# Input.net
KiCad netlist of a schematic drawn in Altium Designer
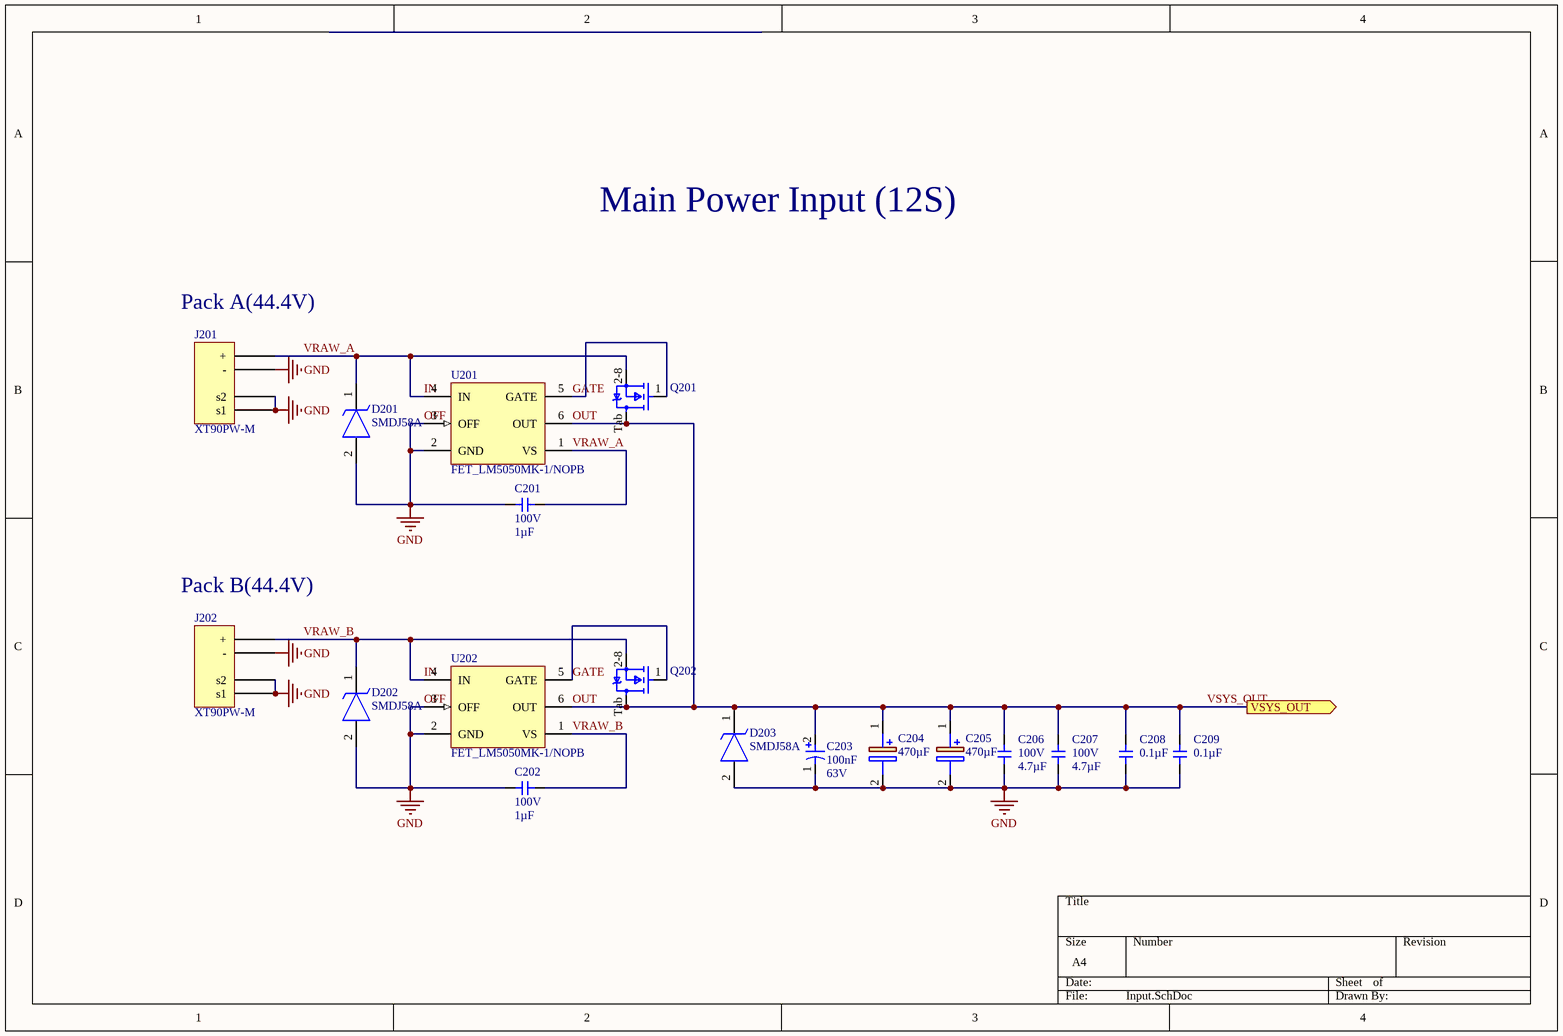
[diagram p0: Input.SchDoc]

(export (version "E")
  (design (tool "Eeschema 10.0.6"))
  (components
    (comp (ref "C201")
      (value "non-polar_Capacitor")
      (footprint "1206")
      (description "SMD type ceramic capacitor")
      (fields
        (field (name "VOLTAGE") "100V")
        (field (name "CAPACITANCE") "1µF")
        (field (name "SOURCE") "robit_passive.SchLib")
      )
      (libsource (lib "robit circuit") (part "Capacitor"))
    )
    (comp (ref "C202")
      (value "non-polar_Capacitor")
      (footprint "1206")
      (description "SMD type ceramic capacitor")
      (fields
        (field (name "VOLTAGE") "100V")
        (field (name "CAPACITANCE") "1µF")
        (field (name "SOURCE") "robit_passive.SchLib")
      )
      (libsource (lib "robit circuit") (part "Capacitor"))
    )
    (comp (ref "C203")
      (value "Capacitor_tantal")
      (footprint "SMD_Capacitor_tantal")
      (description "SMD type tantalum capacitor")
      (fields
        (field (name "CAPACITANCE") "100nF")
        (field (name "VOLTAGE") "63V")
        (field (name "SOURCE") "robit_passive.SchLib")
      )
      (libsource (lib "robit circuit") (part "Capacitor_tantal"))
    )
    (comp (ref "C204")
      (value "470µF")
      (footprint "SamacSys:CAPAE1900X2200N")
      (description "Capacitor Polarised")
      (fields
        (field (name "MANUFACTURER_PART_NUMBER") "MAL215099913E3")
        (field (name "MOUSER PART NUMBER") "594-MAL215099913E3")
      )
      (libsource (lib "*") (part "MAL215099913E3"))
    )
    (comp (ref "C205")
      (value "470µF")
      (footprint "SamacSys:CAPAE1900X2200N")
      (description "Capacitor Polarised")
      (fields
        (field (name "MANUFACTURER_PART_NUMBER") "MAL215099913E3")
        (field (name "MOUSER PART NUMBER") "594-MAL215099913E3")
      )
      (libsource (lib "*") (part "MAL215099913E3"))
    )
    (comp (ref "C206")
      (value "non-polar_Capacitor")
      (footprint "1210")
      (description "SMD type ceramic capacitor")
      (fields
        (field (name "VOLTAGE") "100V")
        (field (name "CAPACITANCE") "4.7µF")
        (field (name "SOURCE") "robit_passive.SchLib")
      )
      (libsource (lib "robit circuit") (part "Capacitor"))
    )
    (comp (ref "C207")
      (value "non-polar_Capacitor")
      (footprint "1210")
      (description "SMD type ceramic capacitor")
      (fields
        (field (name "VOLTAGE") "100V")
        (field (name "CAPACITANCE") "4.7µF")
        (field (name "SOURCE") "robit_passive.SchLib")
      )
      (libsource (lib "robit circuit") (part "Capacitor"))
    )
    (comp (ref "C208")
      (value "non-polar_Capacitor")
      (footprint "0603")
      (description "SMD type ceramic capacitor")
      (fields
        (field (name "VOLTAGE") "100V")
        (field (name "CAPACITANCE") "0.1µF")
        (field (name "SOURCE") "robit_passive.SchLib")
      )
      (libsource (lib "robit circuit") (part "Capacitor"))
    )
    (comp (ref "C209")
      (value "non-polar_Capacitor")
      (footprint "0603")
      (description "SMD type ceramic capacitor")
      (fields
        (field (name "VOLTAGE") "100V")
        (field (name "CAPACITANCE") "0.1µF")
        (field (name "SOURCE") "robit_passive.SchLib")
      )
      (libsource (lib "robit circuit") (part "Capacitor"))
    )
    (comp (ref "D201")
      (value "SMDJ58A")
      (footprint "SamacSys:DIONM7959X262N")
      (description "TVS Diode (Uni-directional)")
      (fields (field (name "MOUSER PART NUMBER") "576-SMDJ58A"))
      (libsource (lib "*") (part "SMDJ58A"))
    )
    (comp (ref "D202")
      (value "SMDJ58A")
      (footprint "SamacSys:DIONM7959X262N")
      (description "TVS Diode (Uni-directional)")
      (fields (field (name "MOUSER PART NUMBER") "576-SMDJ58A"))
      (libsource (lib "*") (part "SMDJ58A"))
    )
    (comp (ref "D203")
      (value "SMDJ58A")
      (footprint "SamacSys:DIONM7959X262N")
      (description "TVS Diode (Uni-directional)")
      (fields (field (name "MOUSER PART NUMBER") "576-SMDJ58A"))
      (libsource (lib "*") (part "SMDJ58A"))
    )
    (comp (ref "J201")
      (value "XT90PW-M")
      (footprint "AMASS_XT90PW-M")
      (description "Socket; DC supply; XT90; male; PIN: 2; on PCBs; THT; Colour: yellow")
      (fields (field (name "MF") "AMASS"))
      (libsource (lib "robit circuit") (part "XT90PW-M"))
    )
    (comp (ref "J202")
      (value "XT90PW-M")
      (footprint "AMASS_XT90PW-M")
      (description "Socket; DC supply; XT90; male; PIN: 2; on PCBs; THT; Colour: yellow")
      (fields (field (name "MF") "AMASS"))
      (libsource (lib "robit circuit") (part "XT90PW-M"))
    )
    (comp (ref "Q201")
      (value "Trans_Infineon_IPT015N10N5_eec")
      (footprint "Infineon_IPT015N10N5_0")
      (description "TRANS MOSFET N-CH 100V 300A 8HSOF")
      (fields (field (name "PART NUMBER") "IPT015N10N5") (field (name "MANUFACTURER") "Infineon"))
      (libsource (lib "Trans_Infineon_IPT015N10N5_eec") (part "Trans_Infineon_IPT015N10N5_eec"))
    )
    (comp (ref "Q202")
      (value "Trans_Infineon_IPT015N10N5_eec")
      (footprint "Infineon_IPT015N10N5_0")
      (description "TRANS MOSFET N-CH 100V 300A 8HSOF")
      (fields (field (name "PART NUMBER") "IPT015N10N5") (field (name "MANUFACTURER") "Infineon"))
      (libsource (lib "Trans_Infineon_IPT015N10N5_eec") (part "Trans_Infineon_IPT015N10N5_eec"))
    )
    (comp (ref "U201")
      (value "FET_LM5050MK-1/NOPB")
      (footprint "DDC0006A_M")
      (description "5-V to 75-V 400-uA IQ ORing FET controller 6-SOT-23-THIN -40 to 125")
      (libsource (lib "robit circuit") (part "PM-SMPS-LM5050-IL6"))
    )
    (comp (ref "U202")
      (value "FET_LM5050MK-1/NOPB")
      (footprint "DDC0006A_M")
      (description "5-V to 75-V 400-uA IQ ORing FET controller 6-SOT-23-THIN -40 to 125")
      (libsource (lib "robit circuit") (part "PM-SMPS-LM5050-IL6"))
    )
  )
  (nets
    (net (code "1") (name "/GATE") (class "Default")
      (node (ref "Q201") (pin "1") (pinfunction "Gate_1") (pintype "passive"))
      (node (ref "Q202") (pin "1") (pinfunction "Gate_1") (pintype "passive"))
      (node (ref "U201") (pin "5") (pinfunction "GATE_5") (pintype "power_in"))
      (node (ref "U202") (pin "5") (pinfunction "GATE_5") (pintype "power_in"))
    )
    (net (code "2") (name "/IN") (class "Default")
      (node (ref "C201") (pin "2") (pinfunction "2_2") (pintype "passive"))
      (node (ref "C202") (pin "2") (pinfunction "2_2") (pintype "passive"))
      (node (ref "D201") (pin "1") (pinfunction "K_1") (pintype "passive"))
      (node (ref "D202") (pin "1") (pinfunction "K_1") (pintype "passive"))
      (node (ref "J201") (pin "P") (pinfunction "+_P") (pintype "power_in"))
      (node (ref "J202") (pin "P") (pinfunction "+_P") (pintype "power_in"))
      (node (ref "Q201") (pin "2-8") (pinfunction "Source_2-8") (pintype "passive"))
      (node (ref "Q202") (pin "2-8") (pinfunction "Source_2-8") (pintype "passive"))
      (node (ref "U201") (pin "1") (pinfunction "VS_1") (pintype "power_in"))
      (node (ref "U201") (pin "4") (pinfunction "IN_4") (pintype "power_in"))
      (node (ref "U202") (pin "1") (pinfunction "VS_1") (pintype "power_in"))
      (node (ref "U202") (pin "4") (pinfunction "IN_4") (pintype "power_in"))
    )
    (net (code "3") (name "/OUT") (class "Default")
      (node (ref "C203") (pin "2") (pinfunction "1_2") (pintype "passive"))
      (node (ref "C204") (pin "1") (pinfunction "+_1") (pintype "passive"))
      (node (ref "C205") (pin "1") (pinfunction "+_1") (pintype "passive"))
      (node (ref "C206") (pin "1") (pinfunction "1_1") (pintype "passive"))
      (node (ref "C207") (pin "2") (pinfunction "2_2") (pintype "passive"))
      (node (ref "C208") (pin "2") (pinfunction "2_2") (pintype "passive"))
      (node (ref "C209") (pin "2") (pinfunction "2_2") (pintype "passive"))
      (node (ref "D203") (pin "1") (pinfunction "K_1") (pintype "passive"))
      (node (ref "Q201") (pin "Tab") (pinfunction "Drain_Tab") (pintype "passive"))
      (node (ref "Q202") (pin "Tab") (pinfunction "Drain_Tab") (pintype "passive"))
      (node (ref "U201") (pin "6") (pinfunction "OUT_6") (pintype "passive"))
      (node (ref "U202") (pin "6") (pinfunction "OUT_6") (pintype "passive"))
    )
    (net (code "4") (name "GND") (class "Default")
      (node (ref "C201") (pin "1") (pinfunction "1_1") (pintype "passive"))
      (node (ref "C202") (pin "1") (pinfunction "1_1") (pintype "passive"))
      (node (ref "C203") (pin "1") (pinfunction "0_1") (pintype "passive"))
      (node (ref "C204") (pin "2") (pinfunction "-_2") (pintype "passive"))
      (node (ref "C205") (pin "2") (pinfunction "-_2") (pintype "passive"))
      (node (ref "C206") (pin "2") (pinfunction "2_2") (pintype "passive"))
      (node (ref "C207") (pin "1") (pinfunction "1_1") (pintype "passive"))
      (node (ref "C208") (pin "1") (pinfunction "1_1") (pintype "passive"))
      (node (ref "C209") (pin "1") (pinfunction "1_1") (pintype "passive"))
      (node (ref "D201") (pin "2") (pinfunction "A_2") (pintype "passive"))
      (node (ref "D202") (pin "2") (pinfunction "A_2") (pintype "passive"))
      (node (ref "D203") (pin "2") (pinfunction "A_2") (pintype "passive"))
      (node (ref "J201") (pin "N") (pinfunction "-_N") (pintype "power_in"))
      (node (ref "J201") (pin "S1") (pinfunction "s1_S1") (pintype "power_in"))
      (node (ref "J201") (pin "S2") (pinfunction "s2_S2") (pintype "power_in"))
      (node (ref "J202") (pin "N") (pinfunction "-_N") (pintype "power_in"))
      (node (ref "J202") (pin "S1") (pinfunction "s1_S1") (pintype "power_in"))
      (node (ref "J202") (pin "S2") (pinfunction "s2_S2") (pintype "power_in"))
      (node (ref "U201") (pin "2") (pinfunction "GND_2") (pintype "power_in"))
      (node (ref "U201") (pin "3") (pinfunction "OFF_3") (pintype "input"))
      (node (ref "U202") (pin "2") (pinfunction "GND_2") (pintype "power_in"))
      (node (ref "U202") (pin "3") (pinfunction "OFF_3") (pintype "input"))
    )
  )
)
